# shemLamps.net
KiCad netlist of a schematic drawn in EAGLE
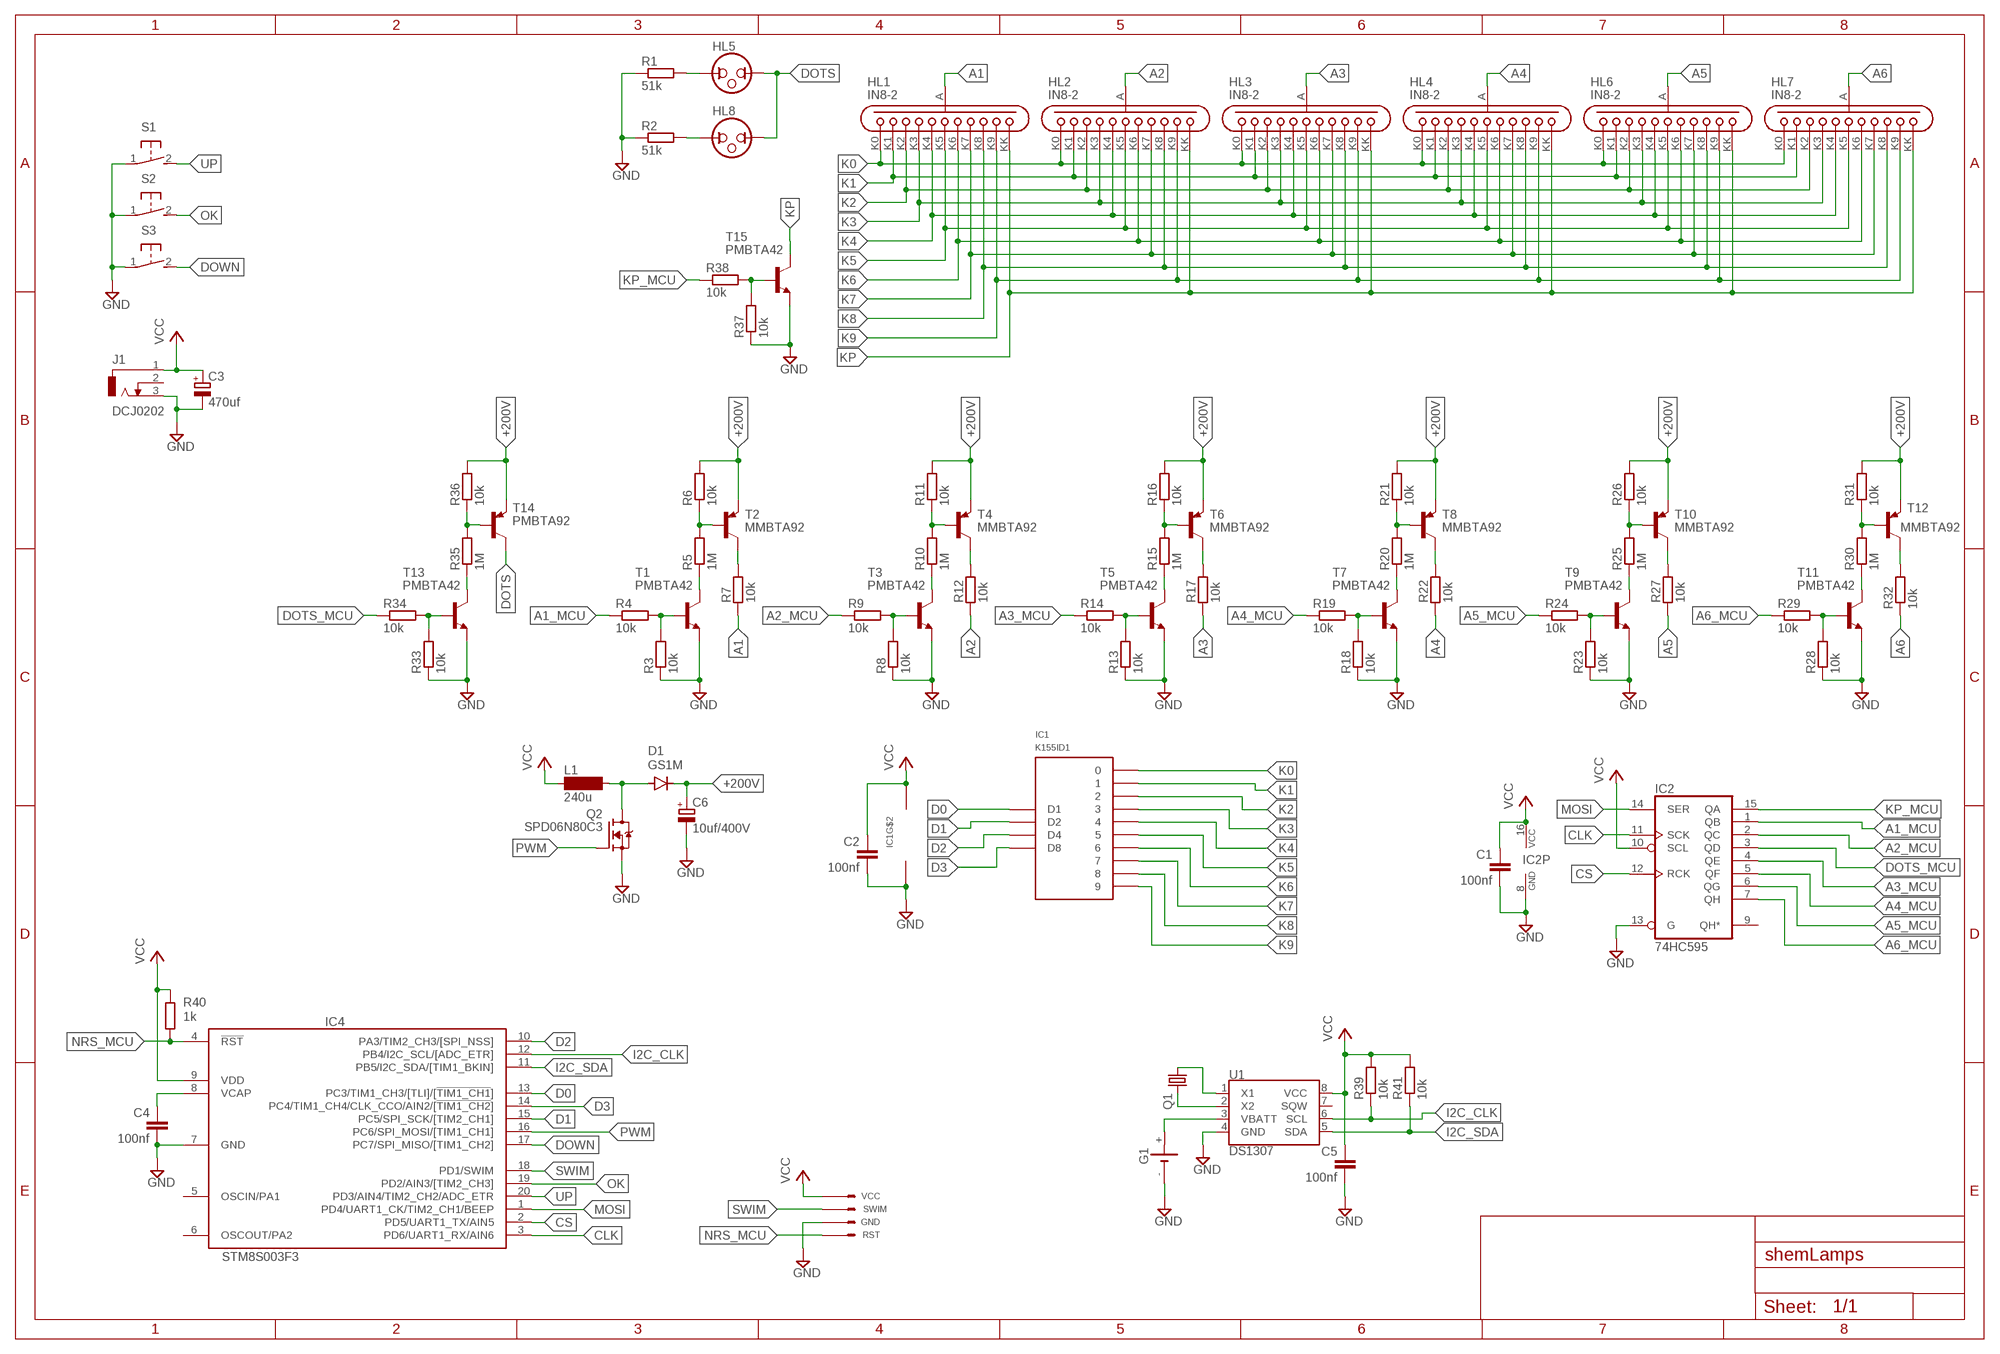
[diagram p0: schematic, sheet 1]

(export (version "E")
  (design (tool "Eeschema 10.0.6"))
  (components
    (comp (ref "C1")
      (value "100nf")
      (footprint "eagle-import:C0805")
      (libsource (lib "eagle-import") (part "CAP"))
    )
    (comp (ref "C2")
      (value "100nf")
      (footprint "eagle-import:C0805")
      (libsource (lib "eagle-import") (part "CAP"))
    )
    (comp (ref "C3")
      (value "470uf")
      (footprint "eagle-import:E3,5-8")
      (libsource (lib "eagle-import") (part "CPOL-EUE3.5-8"))
    )
    (comp (ref "C4")
      (value "100nf")
      (footprint "eagle-import:C0805")
      (libsource (lib "eagle-import") (part "CAP"))
    )
    (comp (ref "C5")
      (value "100nf")
      (footprint "eagle-import:C0805")
      (libsource (lib "eagle-import") (part "CAP"))
    )
    (comp (ref "C6")
      (value "10uf/400V")
      (footprint "eagle-import:E3,5-8")
      (libsource (lib "eagle-import") (part "CPOL-EUE3.5-8"))
    )
    (comp (ref "D1")
      (value "GS1M")
      (footprint "eagle-import:DO-214AC")
      (libsource (lib "eagle-import") (part "DIODE-DO-214AC"))
    )
    (comp (ref "G1")
      (value "BATTERY")
      (footprint "eagle-import:CH291-1220LF_W")
      (libsource (lib "eagle-import") (part "BATTERY"))
    )
    (comp (ref "HL1")
      (value "IN8-2")
      (footprint "eagle-import:IN8-2")
      (libsource (lib "eagle-import") (part "IN8-2"))
    )
    (comp (ref "HL2")
      (value "IN8-2")
      (footprint "eagle-import:IN8-2")
      (libsource (lib "eagle-import") (part "IN8-2"))
    )
    (comp (ref "HL3")
      (value "IN8-2")
      (footprint "eagle-import:IN8-2")
      (libsource (lib "eagle-import") (part "IN8-2"))
    )
    (comp (ref "HL4")
      (value "IN8-2")
      (footprint "eagle-import:IN8-2")
      (libsource (lib "eagle-import") (part "IN8-2"))
    )
    (comp (ref "HL5")
      (value "NEON_LAMP")
      (footprint "eagle-import:NEON_LAMP")
      (libsource (lib "eagle-import") (part "NEON_LAMP"))
    )
    (comp (ref "HL6")
      (value "IN8-2")
      (footprint "eagle-import:IN8-2")
      (libsource (lib "eagle-import") (part "IN8-2"))
    )
    (comp (ref "HL7")
      (value "IN8-2")
      (footprint "eagle-import:IN8-2")
      (libsource (lib "eagle-import") (part "IN8-2"))
    )
    (comp (ref "HL8")
      (value "NEON_LAMP")
      (footprint "eagle-import:NEON_LAMP")
      (libsource (lib "eagle-import") (part "NEON_LAMP"))
    )
    (comp (ref "IC1")
      (value "K155ID1")
      (footprint "eagle-import:DIL16")
      (libsource (lib "eagle-import") (part "K155ID1"))
    )
    (comp (ref "IC2")
      (value "74HC595")
      (footprint "eagle-import:TSSOP16L")
      (libsource (lib "eagle-import") (part "74HC595"))
    )
    (comp (ref "IC4")
      (value "STM8S003F3")
      (footprint "eagle-import:TSSOP20")
      (libsource (lib "eagle-import") (part "STM8S003F3"))
    )
    (comp (ref "J1")
      (value "DCJ0202")
      (footprint "eagle-import:DCJ0202")
      (libsource (lib "eagle-import") (part "DCJ0202"))
    )
    (comp (ref "L1")
      (value "240u")
      (footprint "eagle-import:BS11")
      (libsource (lib "eagle-import") (part "BS11"))
    )
    (comp (ref "Q1")
      (value "CRYSTALTC26H")
      (footprint "eagle-import:TC26H")
      (libsource (lib "eagle-import") (part "CRYSTALTC26H"))
    )
    (comp (ref "Q2")
      (value "SPD06N80C3")
      (footprint "eagle-import:TO252")
      (libsource (lib "eagle-import") (part "SPD06N80C3"))
    )
    (comp (ref "R1")
      (value "51k")
      (footprint "eagle-import:0207_10")
      (libsource (lib "eagle-import") (part "R-EU_0207/10"))
    )
    (comp (ref "R2")
      (value "51k")
      (footprint "eagle-import:0207_10")
      (libsource (lib "eagle-import") (part "R-EU_0207/10"))
    )
    (comp (ref "R3")
      (value "10k")
      (footprint "eagle-import:R0805")
      (libsource (lib "eagle-import") (part "RES"))
    )
    (comp (ref "R4")
      (value "10k")
      (footprint "eagle-import:R0805")
      (libsource (lib "eagle-import") (part "RES"))
    )
    (comp (ref "R5")
      (value "1M")
      (footprint "eagle-import:R0805")
      (libsource (lib "eagle-import") (part "RES"))
    )
    (comp (ref "R6")
      (value "10k")
      (footprint "eagle-import:R0805")
      (libsource (lib "eagle-import") (part "RES"))
    )
    (comp (ref "R7")
      (value "10k")
      (footprint "eagle-import:R0805")
      (libsource (lib "eagle-import") (part "RES"))
    )
    (comp (ref "R8")
      (value "10k")
      (footprint "eagle-import:R0805")
      (libsource (lib "eagle-import") (part "RES"))
    )
    (comp (ref "R9")
      (value "10k")
      (footprint "eagle-import:R0805")
      (libsource (lib "eagle-import") (part "RES"))
    )
    (comp (ref "R10")
      (value "1M")
      (footprint "eagle-import:R0805")
      (libsource (lib "eagle-import") (part "RES"))
    )
    (comp (ref "R11")
      (value "10k")
      (footprint "eagle-import:R0805")
      (libsource (lib "eagle-import") (part "RES"))
    )
    (comp (ref "R12")
      (value "10k")
      (footprint "eagle-import:R0805")
      (libsource (lib "eagle-import") (part "RES"))
    )
    (comp (ref "R13")
      (value "10k")
      (footprint "eagle-import:R0805")
      (libsource (lib "eagle-import") (part "RES"))
    )
    (comp (ref "R14")
      (value "10k")
      (footprint "eagle-import:R0805")
      (libsource (lib "eagle-import") (part "RES"))
    )
    (comp (ref "R15")
      (value "1M")
      (footprint "eagle-import:R0805")
      (libsource (lib "eagle-import") (part "RES"))
    )
    (comp (ref "R16")
      (value "10k")
      (footprint "eagle-import:R0805")
      (libsource (lib "eagle-import") (part "RES"))
    )
    (comp (ref "R17")
      (value "10k")
      (footprint "eagle-import:R0805")
      (libsource (lib "eagle-import") (part "RES"))
    )
    (comp (ref "R18")
      (value "10k")
      (footprint "eagle-import:R0805")
      (libsource (lib "eagle-import") (part "RES"))
    )
    (comp (ref "R19")
      (value "10k")
      (footprint "eagle-import:R0805")
      (libsource (lib "eagle-import") (part "RES"))
    )
    (comp (ref "R20")
      (value "1M")
      (footprint "eagle-import:R0805")
      (libsource (lib "eagle-import") (part "RES"))
    )
    (comp (ref "R21")
      (value "10k")
      (footprint "eagle-import:R0805")
      (libsource (lib "eagle-import") (part "RES"))
    )
    (comp (ref "R22")
      (value "10k")
      (footprint "eagle-import:R0805")
      (libsource (lib "eagle-import") (part "RES"))
    )
    (comp (ref "R23")
      (value "10k")
      (footprint "eagle-import:R0805")
      (libsource (lib "eagle-import") (part "RES"))
    )
    (comp (ref "R24")
      (value "10k")
      (footprint "eagle-import:R0805")
      (libsource (lib "eagle-import") (part "RES"))
    )
    (comp (ref "R25")
      (value "1M")
      (footprint "eagle-import:R0805")
      (libsource (lib "eagle-import") (part "RES"))
    )
    (comp (ref "R26")
      (value "10k")
      (footprint "eagle-import:R0805")
      (libsource (lib "eagle-import") (part "RES"))
    )
    (comp (ref "R27")
      (value "10k")
      (footprint "eagle-import:R0805")
      (libsource (lib "eagle-import") (part "RES"))
    )
    (comp (ref "R28")
      (value "10k")
      (footprint "eagle-import:R0805")
      (libsource (lib "eagle-import") (part "RES"))
    )
    (comp (ref "R29")
      (value "10k")
      (footprint "eagle-import:R0805")
      (libsource (lib "eagle-import") (part "RES"))
    )
    (comp (ref "R30")
      (value "1M")
      (footprint "eagle-import:R0805")
      (libsource (lib "eagle-import") (part "RES"))
    )
    (comp (ref "R31")
      (value "10k")
      (footprint "eagle-import:R0805")
      (libsource (lib "eagle-import") (part "RES"))
    )
    (comp (ref "R32")
      (value "10k")
      (footprint "eagle-import:R0805")
      (libsource (lib "eagle-import") (part "RES"))
    )
    (comp (ref "R33")
      (value "10k")
      (footprint "eagle-import:R0805")
      (libsource (lib "eagle-import") (part "RES"))
    )
    (comp (ref "R34")
      (value "10k")
      (footprint "eagle-import:R0805")
      (libsource (lib "eagle-import") (part "RES"))
    )
    (comp (ref "R35")
      (value "1M")
      (footprint "eagle-import:R0805")
      (libsource (lib "eagle-import") (part "RES"))
    )
    (comp (ref "R36")
      (value "10k")
      (footprint "eagle-import:R0805")
      (libsource (lib "eagle-import") (part "RES"))
    )
    (comp (ref "R37")
      (value "10k")
      (footprint "eagle-import:R0805")
      (libsource (lib "eagle-import") (part "RES"))
    )
    (comp (ref "R38")
      (value "10k")
      (footprint "eagle-import:R0805")
      (libsource (lib "eagle-import") (part "RES"))
    )
    (comp (ref "R39")
      (value "10k")
      (footprint "eagle-import:R0805")
      (libsource (lib "eagle-import") (part "RES"))
    )
    (comp (ref "R40")
      (value "1k")
      (footprint "eagle-import:R0805")
      (libsource (lib "eagle-import") (part "RES"))
    )
    (comp (ref "R41")
      (value "10k")
      (footprint "eagle-import:R0805")
      (libsource (lib "eagle-import") (part "RES"))
    )
    (comp (ref "S1")
      (value "31-XX")
      (footprint "eagle-import:B3F-31XX")
      (fields (field (name "MPN") "B3F-3100"))
      (libsource (lib "eagle-import") (part "31-XX"))
    )
    (comp (ref "S2")
      (value "31-XX")
      (footprint "eagle-import:B3F-31XX")
      (fields (field (name "MPN") "B3F-3100"))
      (libsource (lib "eagle-import") (part "31-XX"))
    )
    (comp (ref "S3")
      (value "31-XX")
      (footprint "eagle-import:B3F-31XX")
      (fields (field (name "MPN") "B3F-3100"))
      (libsource (lib "eagle-import") (part "31-XX"))
    )
    (comp (ref "SV1")
      (value "SWIM")
      (footprint "eagle-import:SWIM")
      (libsource (lib "eagle-import") (part "SWIM"))
    )
    (comp (ref "T1")
      (value "PMBTA42")
      (footprint "eagle-import:SOT23-BEC")
      (libsource (lib "eagle-import") (part "-NPN-SOT23-BECBC817-16"))
    )
    (comp (ref "T2")
      (value "MMBTA92")
      (footprint "eagle-import:SOT23-BEC")
      (libsource (lib "eagle-import") (part "-PNP-SOT23-BECBC807-16"))
    )
    (comp (ref "T3")
      (value "PMBTA42")
      (footprint "eagle-import:SOT23-BEC")
      (libsource (lib "eagle-import") (part "-NPN-SOT23-BECBC817-16"))
    )
    (comp (ref "T4")
      (value "MMBTA92")
      (footprint "eagle-import:SOT23-BEC")
      (libsource (lib "eagle-import") (part "-PNP-SOT23-BECBC807-16"))
    )
    (comp (ref "T5")
      (value "PMBTA42")
      (footprint "eagle-import:SOT23-BEC")
      (libsource (lib "eagle-import") (part "-NPN-SOT23-BECBC817-16"))
    )
    (comp (ref "T6")
      (value "MMBTA92")
      (footprint "eagle-import:SOT23-BEC")
      (libsource (lib "eagle-import") (part "-PNP-SOT23-BECBC807-16"))
    )
    (comp (ref "T7")
      (value "PMBTA42")
      (footprint "eagle-import:SOT23-BEC")
      (libsource (lib "eagle-import") (part "-NPN-SOT23-BECBC817-16"))
    )
    (comp (ref "T8")
      (value "MMBTA92")
      (footprint "eagle-import:SOT23-BEC")
      (libsource (lib "eagle-import") (part "-PNP-SOT23-BECBC807-16"))
    )
    (comp (ref "T9")
      (value "PMBTA42")
      (footprint "eagle-import:SOT23-BEC")
      (libsource (lib "eagle-import") (part "-NPN-SOT23-BECBC817-16"))
    )
    (comp (ref "T10")
      (value "MMBTA92")
      (footprint "eagle-import:SOT23-BEC")
      (libsource (lib "eagle-import") (part "-PNP-SOT23-BECBC807-16"))
    )
    (comp (ref "T11")
      (value "PMBTA42")
      (footprint "eagle-import:SOT23-BEC")
      (libsource (lib "eagle-import") (part "-NPN-SOT23-BECBC817-16"))
    )
    (comp (ref "T12")
      (value "MMBTA92")
      (footprint "eagle-import:SOT23-BEC")
      (libsource (lib "eagle-import") (part "-PNP-SOT23-BECBC807-16"))
    )
    (comp (ref "T13")
      (value "PMBTA42")
      (footprint "eagle-import:SOT23-BEC")
      (libsource (lib "eagle-import") (part "-NPN-SOT23-BECBC817-16"))
    )
    (comp (ref "T14")
      (value "PMBTA92")
      (footprint "eagle-import:SOT23-BEC")
      (libsource (lib "eagle-import") (part "-PNP-SOT23-BECBC807-16"))
    )
    (comp (ref "T15")
      (value "PMBTA42")
      (footprint "eagle-import:SOT23-BEC")
      (libsource (lib "eagle-import") (part "-NPN-SOT23-BECBC817-16"))
    )
    (comp (ref "U1")
      (value "DS1307")
      (footprint "eagle-import:SO08")
      (libsource (lib "eagle-import") (part "DS1307"))
    )
  )
  (nets
    (net (code "1") (name "+200V") (class "Default")
      (node (ref "C6") (pin "+") (pinfunction "+_+") (pintype "passive"))
      (node (ref "D1") (pin "C") (pinfunction "C_C") (pintype "passive"))
      (node (ref "R11") (pin "2") (pinfunction "2_2") (pintype "passive"))
      (node (ref "R16") (pin "2") (pinfunction "2_2") (pintype "passive"))
      (node (ref "R21") (pin "2") (pinfunction "2_2") (pintype "passive"))
      (node (ref "R26") (pin "2") (pinfunction "2_2") (pintype "passive"))
      (node (ref "R31") (pin "2") (pinfunction "2_2") (pintype "passive"))
      (node (ref "R36") (pin "2") (pinfunction "2_2") (pintype "passive"))
      (node (ref "R6") (pin "2") (pinfunction "2_2") (pintype "passive"))
      (node (ref "T10") (pin "E") (pinfunction "E_E") (pintype "passive"))
      (node (ref "T12") (pin "E") (pinfunction "E_E") (pintype "passive"))
      (node (ref "T14") (pin "E") (pinfunction "E_E") (pintype "passive"))
      (node (ref "T2") (pin "E") (pinfunction "E_E") (pintype "passive"))
      (node (ref "T4") (pin "E") (pinfunction "E_E") (pintype "passive"))
      (node (ref "T6") (pin "E") (pinfunction "E_E") (pintype "passive"))
      (node (ref "T8") (pin "E") (pinfunction "E_E") (pintype "passive"))
    )
    (net (code "2") (name "A1") (class "Default")
      (node (ref "HL1") (pin "A") (pinfunction "A_A") (pintype "passive"))
      (node (ref "R7") (pin "1") (pinfunction "1_1") (pintype "passive"))
    )
    (net (code "3") (name "A1_MCU") (class "Default")
      (node (ref "IC2") (pin "1") (pinfunction "QB_1") (pintype "tri_state"))
      (node (ref "R4") (pin "1") (pinfunction "1_1") (pintype "passive"))
    )
    (net (code "4") (name "A2") (class "Default")
      (node (ref "HL2") (pin "A") (pinfunction "A_A") (pintype "passive"))
      (node (ref "R12") (pin "1") (pinfunction "1_1") (pintype "passive"))
    )
    (net (code "5") (name "A2_MCU") (class "Default")
      (node (ref "IC2") (pin "2") (pinfunction "QC_2") (pintype "tri_state"))
      (node (ref "R9") (pin "1") (pinfunction "1_1") (pintype "passive"))
    )
    (net (code "6") (name "A3") (class "Default")
      (node (ref "HL3") (pin "A") (pinfunction "A_A") (pintype "passive"))
      (node (ref "R17") (pin "1") (pinfunction "1_1") (pintype "passive"))
    )
    (net (code "7") (name "A3_MCU") (class "Default")
      (node (ref "IC2") (pin "4") (pinfunction "QE_4") (pintype "tri_state"))
      (node (ref "R14") (pin "1") (pinfunction "1_1") (pintype "passive"))
    )
    (net (code "8") (name "A4") (class "Default")
      (node (ref "HL4") (pin "A") (pinfunction "A_A") (pintype "passive"))
      (node (ref "R22") (pin "1") (pinfunction "1_1") (pintype "passive"))
    )
    (net (code "9") (name "A4_MCU") (class "Default")
      (node (ref "IC2") (pin "5") (pinfunction "QF_5") (pintype "tri_state"))
      (node (ref "R19") (pin "1") (pinfunction "1_1") (pintype "passive"))
    )
    (net (code "10") (name "A5") (class "Default")
      (node (ref "HL6") (pin "A") (pinfunction "A_A") (pintype "passive"))
      (node (ref "R27") (pin "1") (pinfunction "1_1") (pintype "passive"))
    )
    (net (code "11") (name "A5_MCU") (class "Default")
      (node (ref "IC2") (pin "6") (pinfunction "QG_6") (pintype "tri_state"))
      (node (ref "R24") (pin "1") (pinfunction "1_1") (pintype "passive"))
    )
    (net (code "12") (name "A6") (class "Default")
      (node (ref "HL7") (pin "A") (pinfunction "A_A") (pintype "passive"))
      (node (ref "R32") (pin "1") (pinfunction "1_1") (pintype "passive"))
    )
    (net (code "13") (name "A6_MCU") (class "Default")
      (node (ref "IC2") (pin "7") (pinfunction "QH_7") (pintype "tri_state"))
      (node (ref "R29") (pin "1") (pinfunction "1_1") (pintype "passive"))
    )
    (net (code "14") (name "CLK") (class "Default")
      (node (ref "IC2") (pin "11") (pinfunction "SCK_11") (pintype "input"))
      (node (ref "IC4") (pin "3") (pinfunction "PD6/UART1_RX/AIN6_3") (pintype "bidirectional"))
    )
    (net (code "15") (name "CS") (class "Default")
      (node (ref "IC2") (pin "12") (pinfunction "RCK_12") (pintype "input"))
      (node (ref "IC4") (pin "2") (pinfunction "PD5/UART1_TX/AIN5_2") (pintype "bidirectional"))
    )
    (net (code "16") (name "D0") (class "Default")
      (node (ref "IC1") (pin "3") (pinfunction "D1_3") (pintype "input"))
      (node (ref "IC4") (pin "13") (pinfunction "PC3/TIM1_CH3/[TLI]/[~{TIM1_CH1}]_13") (pintype "bidirectional"))
    )
    (net (code "17") (name "D1") (class "Default")
      (node (ref "IC1") (pin "6") (pinfunction "D2_6") (pintype "input"))
      (node (ref "IC4") (pin "15") (pinfunction "PC5/SPI_SCK/[TIM2_CH1]_15") (pintype "bidirectional"))
    )
    (net (code "18") (name "D2") (class "Default")
      (node (ref "IC1") (pin "7") (pinfunction "D4_7") (pintype "input"))
      (node (ref "IC4") (pin "10") (pinfunction "PA3/TIM2_CH3/[SPI_NSS]_10") (pintype "bidirectional"))
    )
    (net (code "19") (name "D3") (class "Default")
      (node (ref "IC1") (pin "4") (pinfunction "D8_4") (pintype "input"))
      (node (ref "IC4") (pin "14") (pinfunction "PC4/TIM1_CH4/CLK_CCO/AIN2/[~{TIM1_CH2}]_14") (pintype "bidirectional"))
    )
    (net (code "20") (name "DOTS") (class "Default")
      (node (ref "HL5") (pin "2") (pinfunction "2_2") (pintype "passive"))
      (node (ref "HL8") (pin "2") (pinfunction "2_2") (pintype "passive"))
      (node (ref "T14") (pin "C") (pinfunction "C_C") (pintype "passive"))
    )
    (net (code "21") (name "DOTS_MCU") (class "Default")
      (node (ref "IC2") (pin "3") (pinfunction "QD_3") (pintype "tri_state"))
      (node (ref "R34") (pin "1") (pinfunction "1_1") (pintype "passive"))
    )
    (net (code "22") (name "DOWN") (class "Default")
      (node (ref "IC4") (pin "17") (pinfunction "PC7/SPI_MISO/[TIM1_CH2]_17") (pintype "bidirectional"))
      (node (ref "S3") (pin "2") (pinfunction "S_2") (pintype "passive"))
    )
    (net (code "23") (name "GND") (class "Default")
      (node (ref "C1") (pin "2") (pinfunction "2_2") (pintype "passive"))
      (node (ref "C2") (pin "2") (pinfunction "2_2") (pintype "passive"))
      (node (ref "C3") (pin "-") (pinfunction "-_-") (pintype "passive"))
      (node (ref "C4") (pin "2") (pinfunction "2_2") (pintype "passive"))
      (node (ref "C5") (pin "2") (pinfunction "2_2") (pintype "passive"))
      (node (ref "C6") (pin "-") (pinfunction "-_-") (pintype "passive"))
      (node (ref "G1") (pin "-") (pinfunction "-_-") (pintype "passive"))
      (node (ref "IC1") (pin "12") (pinfunction "GND_12") (pintype "power_in"))
      (node (ref "IC2") (pin "13") (pinfunction "G_13") (pintype "input"))
      (node (ref "IC2") (pin "8") (pinfunction "GND_8") (pintype "power_in"))
      (node (ref "IC4") (pin "7") (pinfunction "GND_7") (pintype "power_in"))
      (node (ref "J1") (pin "3") (pinfunction "3_3") (pintype "passive"))
      (node (ref "Q2") (pin "2") (pinfunction "S_2") (pintype "passive"))
      (node (ref "R1") (pin "1") (pinfunction "1_1") (pintype "passive"))
      (node (ref "R13") (pin "1") (pinfunction "1_1") (pintype "passive"))
      (node (ref "R18") (pin "1") (pinfunction "1_1") (pintype "passive"))
      (node (ref "R2") (pin "1") (pinfunction "1_1") (pintype "passive"))
      (node (ref "R23") (pin "1") (pinfunction "1_1") (pintype "passive"))
      (node (ref "R28") (pin "1") (pinfunction "1_1") (pintype "passive"))
      (node (ref "R3") (pin "1") (pinfunction "1_1") (pintype "passive"))
      (node (ref "R33") (pin "1") (pinfunction "1_1") (pintype "passive"))
      (node (ref "R37") (pin "1") (pinfunction "1_1") (pintype "passive"))
      (node (ref "R8") (pin "1") (pinfunction "1_1") (pintype "passive"))
      (node (ref "S1") (pin "1") (pinfunction "P_1") (pintype "passive"))
      (node (ref "S2") (pin "1") (pinfunction "P_1") (pintype "passive"))
      (node (ref "S3") (pin "1") (pinfunction "P_1") (pintype "passive"))
      (node (ref "SV1") (pin "GND") (pinfunction "GND_GND") (pintype "power_in"))
      (node (ref "T1") (pin "E") (pinfunction "E_E") (pintype "passive"))
      (node (ref "T11") (pin "E") (pinfunction "E_E") (pintype "passive"))
      (node (ref "T13") (pin "E") (pinfunction "E_E") (pintype "passive"))
      (node (ref "T15") (pin "E") (pinfunction "E_E") (pintype "passive"))
      (node (ref "T3") (pin "E") (pinfunction "E_E") (pintype "passive"))
      (node (ref "T5") (pin "E") (pinfunction "E_E") (pintype "passive"))
      (node (ref "T7") (pin "E") (pinfunction "E_E") (pintype "passive"))
      (node (ref "T9") (pin "E") (pinfunction "E_E") (pintype "passive"))
      (node (ref "U1") (pin "4") (pinfunction "GND_4") (pintype "bidirectional"))
    )
    (net (code "24") (name "I2C_CLK") (class "Default")
      (node (ref "IC4") (pin "12") (pinfunction "PB4/I2C_SCL/[ADC_ETR]_12") (pintype "bidirectional"))
      (node (ref "R39") (pin "1") (pinfunction "1_1") (pintype "passive"))
      (node (ref "U1") (pin "6") (pinfunction "SCL_6") (pintype "bidirectional"))
    )
    (net (code "25") (name "I2C_SDA") (class "Default")
      (node (ref "IC4") (pin "11") (pinfunction "PB5/I2C_SDA/[TIM1_BKIN]_11") (pintype "bidirectional"))
      (node (ref "R41") (pin "1") (pinfunction "1_1") (pintype "passive"))
      (node (ref "U1") (pin "5") (pinfunction "SDA_5") (pintype "bidirectional"))
    )
    (net (code "26") (name "K0") (class "Default")
      (node (ref "HL1") (pin "K0") (pinfunction "K0_K0") (pintype "passive"))
      (node (ref "HL2") (pin "K0") (pinfunction "K0_K0") (pintype "passive"))
      (node (ref "HL3") (pin "K0") (pinfunction "K0_K0") (pintype "passive"))
      (node (ref "HL4") (pin "K0") (pinfunction "K0_K0") (pintype "passive"))
      (node (ref "HL6") (pin "K0") (pinfunction "K0_K0") (pintype "passive"))
      (node (ref "HL7") (pin "K0") (pinfunction "K0_K0") (pintype "passive"))
      (node (ref "IC1") (pin "16") (pinfunction "0_16") (pintype "output"))
    )
    (net (code "27") (name "K1") (class "Default")
      (node (ref "HL1") (pin "K1") (pinfunction "K1_K1") (pintype "passive"))
      (node (ref "HL2") (pin "K1") (pinfunction "K1_K1") (pintype "passive"))
      (node (ref "HL3") (pin "K1") (pinfunction "K1_K1") (pintype "passive"))
      (node (ref "HL4") (pin "K1") (pinfunction "K1_K1") (pintype "passive"))
      (node (ref "HL6") (pin "K1") (pinfunction "K1_K1") (pintype "passive"))
      (node (ref "HL7") (pin "K1") (pinfunction "K1_K1") (pintype "passive"))
      (node (ref "IC1") (pin "15") (pinfunction "1_15") (pintype "output"))
    )
    (net (code "28") (name "K2") (class "Default")
      (node (ref "HL1") (pin "K2") (pinfunction "K2_K2") (pintype "passive"))
      (node (ref "HL2") (pin "K2") (pinfunction "K2_K2") (pintype "passive"))
      (node (ref "HL3") (pin "K2") (pinfunction "K2_K2") (pintype "passive"))
      (node (ref "HL4") (pin "K2") (pinfunction "K2_K2") (pintype "passive"))
      (node (ref "HL6") (pin "K2") (pinfunction "K2_K2") (pintype "passive"))
      (node (ref "HL7") (pin "K2") (pinfunction "K2_K2") (pintype "passive"))
      (node (ref "IC1") (pin "8") (pinfunction "2_8") (pintype "output"))
    )
    (net (code "29") (name "K3") (class "Default")
      (node (ref "HL1") (pin "K3") (pinfunction "K3_K3") (pintype "passive"))
      (node (ref "HL2") (pin "K3") (pinfunction "K3_K3") (pintype "passive"))
      (node (ref "HL3") (pin "K3") (pinfunction "K3_K3") (pintype "passive"))
      (node (ref "HL4") (pin "K3") (pinfunction "K3_K3") (pintype "passive"))
      (node (ref "HL6") (pin "K3") (pinfunction "K3_K3") (pintype "passive"))
      (node (ref "HL7") (pin "K3") (pinfunction "K3_K3") (pintype "passive"))
      (node (ref "IC1") (pin "9") (pinfunction "3_9") (pintype "output"))
    )
    (net (code "30") (name "K4") (class "Default")
      (node (ref "HL1") (pin "K4") (pinfunction "K4_K4") (pintype "passive"))
      (node (ref "HL2") (pin "K4") (pinfunction "K4_K4") (pintype "passive"))
      (node (ref "HL3") (pin "K4") (pinfunction "K4_K4") (pintype "passive"))
      (node (ref "HL4") (pin "K4") (pinfunction "K4_K4") (pintype "passive"))
      (node (ref "HL6") (pin "K4") (pinfunction "K4_K4") (pintype "passive"))
      (node (ref "HL7") (pin "K4") (pinfunction "K4_K4") (pintype "passive"))
      (node (ref "IC1") (pin "13") (pinfunction "4_13") (pintype "output"))
    )
    (net (code "31") (name "K5") (class "Default")
      (node (ref "HL1") (pin "K5") (pinfunction "K5_K5") (pintype "passive"))
      (node (ref "HL2") (pin "K5") (pinfunction "K5_K5") (pintype "passive"))
      (node (ref "HL3") (pin "K5") (pinfunction "K5_K5") (pintype "passive"))
      (node (ref "HL4") (pin "K5") (pinfunction "K5_K5") (pintype "passive"))
      (node (ref "HL6") (pin "K5") (pinfunction "K5_K5") (pintype "passive"))
      (node (ref "HL7") (pin "K5") (pinfunction "K5_K5") (pintype "passive"))
      (node (ref "IC1") (pin "14") (pinfunction "5_14") (pintype "output"))
    )
    (net (code "32") (name "K6") (class "Default")
      (node (ref "HL1") (pin "K6") (pinfunction "K6_K6") (pintype "passive"))
      (node (ref "HL2") (pin "K6") (pinfunction "K6_K6") (pintype "passive"))
      (node (ref "HL3") (pin "K6") (pinfunction "K6_K6") (pintype "passive"))
      (node (ref "HL4") (pin "K6") (pinfunction "K6_K6") (pintype "passive"))
      (node (ref "HL6") (pin "K6") (pinfunction "K6_K6") (pintype "passive"))
      (node (ref "HL7") (pin "K6") (pinfunction "K6_K6") (pintype "passive"))
      (node (ref "IC1") (pin "11") (pinfunction "6_11") (pintype "output"))
    )
    (net (code "33") (name "K7") (class "Default")
      (node (ref "HL1") (pin "K7") (pinfunction "K7_K7") (pintype "passive"))
      (node (ref "HL2") (pin "K7") (pinfunction "K7_K7") (pintype "passive"))
      (node (ref "HL3") (pin "K7") (pinfunction "K7_K7") (pintype "passive"))
      (node (ref "HL4") (pin "K7") (pinfunction "K7_K7") (pintype "passive"))
      (node (ref "HL6") (pin "K7") (pinfunction "K7_K7") (pintype "passive"))
      (node (ref "HL7") (pin "K7") (pinfunction "K7_K7") (pintype "passive"))
      (node (ref "IC1") (pin "10") (pinfunction "7_10") (pintype "output"))
    )
    (net (code "34") (name "K8") (class "Default")
      (node (ref "HL1") (pin "K8") (pinfunction "K8_K8") (pintype "passive"))
      (node (ref "HL2") (pin "K8") (pinfunction "K8_K8") (pintype "passive"))
      (node (ref "HL3") (pin "K8") (pinfunction "K8_K8") (pintype "passive"))
      (node (ref "HL4") (pin "K8") (pinfunction "K8_K8") (pintype "passive"))
      (node (ref "HL6") (pin "K8") (pinfunction "K8_K8") (pintype "passive"))
      (node (ref "HL7") (pin "K8") (pinfunction "K8_K8") (pintype "passive"))
      (node (ref "IC1") (pin "1") (pinfunction "8_1") (pintype "output"))
    )
    (net (code "35") (name "K9") (class "Default")
      (node (ref "HL1") (pin "K9") (pinfunction "K9_K9") (pintype "passive"))
      (node (ref "HL2") (pin "K9") (pinfunction "K9_K9") (pintype "passive"))
      (node (ref "HL3") (pin "K9") (pinfunction "K9_K9") (pintype "passive"))
      (node (ref "HL4") (pin "K9") (pinfunction "K9_K9") (pintype "passive"))
      (node (ref "HL6") (pin "K9") (pinfunction "K9_K9") (pintype "passive"))
      (node (ref "HL7") (pin "K9") (pinfunction "K9_K9") (pintype "passive"))
      (node (ref "IC1") (pin "2") (pinfunction "9_2") (pintype "output"))
    )
    (net (code "36") (name "KP") (class "Default")
      (node (ref "HL1") (pin "KK") (pinfunction "KK_KK") (pintype "passive"))
      (node (ref "HL2") (pin "KK") (pinfunction "KK_KK") (pintype "passive"))
      (node (ref "HL3") (pin "KK") (pinfunction "KK_KK") (pintype "passive"))
      (node (ref "HL4") (pin "KK") (pinfunction "KK_KK") (pintype "passive"))
      (node (ref "HL6") (pin "KK") (pinfunction "KK_KK") (pintype "passive"))
      (node (ref "HL7") (pin "KK") (pinfunction "KK_KK") (pintype "passive"))
      (node (ref "T15") (pin "C") (pinfunction "C_C") (pintype "passive"))
    )
    (net (code "37") (name "KP_MCU") (class "Default")
      (node (ref "IC2") (pin "15") (pinfunction "QA_15") (pintype "tri_state"))
      (node (ref "R38") (pin "1") (pinfunction "1_1") (pintype "passive"))
    )
    (net (code "38") (name "MOSI") (class "Default")
      (node (ref "IC2") (pin "14") (pinfunction "SER_14") (pintype "input"))
      (node (ref "IC4") (pin "1") (pinfunction "PD4/UART1_CK/TIM2_CH1/BEEP_1") (pintype "bidirectional"))
    )
    (net (code "39") (name "NRS_MCU") (class "Default")
      (node (ref "IC4") (pin "4") (pinfunction "~{RST}_4") (pintype "input"))
      (node (ref "R40") (pin "1") (pinfunction "1_1") (pintype "passive"))
      (node (ref "SV1") (pin "NRS") (pinfunction "RST_NRS") (pintype "bidirectional"))
    )
    (net (code "40") (name "Net-(HL5-Pad1)") (class "Default")
      (node (ref "HL5") (pin "1") (pinfunction "1_1") (pintype "passive"))
      (node (ref "R1") (pin "2") (pinfunction "2_2") (pintype "passive"))
    )
    (net (code "41") (name "Net-(HL8-Pad1)") (class "Default")
      (node (ref "HL8") (pin "1") (pinfunction "1_1") (pintype "passive"))
      (node (ref "R2") (pin "2") (pinfunction "2_2") (pintype "passive"))
    )
    (net (code "42") (name "Net-(IC4-VCAP)") (class "Default")
      (node (ref "C4") (pin "1") (pinfunction "1_1") (pintype "passive"))
      (node (ref "IC4") (pin "8") (pinfunction "VCAP_8") (pintype "power_in"))
    )
    (net (code "43") (name "Net-(Q2-D)") (class "Default")
      (node (ref "D1") (pin "A") (pinfunction "A_A") (pintype "passive"))
      (node (ref "L1") (pin "2") (pinfunction "2_2") (pintype "passive"))
      (node (ref "Q2") (pin "3") (pinfunction "D_3") (pintype "passive"))
    )
    (net (code "44") (name "Net-(R3-Pad2)") (class "Default")
      (node (ref "R3") (pin "2") (pinfunction "2_2") (pintype "passive"))
      (node (ref "R4") (pin "2") (pinfunction "2_2") (pintype "passive"))
      (node (ref "T1") (pin "B") (pinfunction "B_B") (pintype "passive"))
    )
    (net (code "45") (name "Net-(R5-Pad1)") (class "Default")
      (node (ref "R5") (pin "1") (pinfunction "1_1") (pintype "passive"))
      (node (ref "T1") (pin "C") (pinfunction "C_C") (pintype "passive"))
    )
    (net (code "46") (name "Net-(R5-Pad2)") (class "Default")
      (node (ref "R5") (pin "2") (pinfunction "2_2") (pintype "passive"))
      (node (ref "R6") (pin "1") (pinfunction "1_1") (pintype "passive"))
      (node (ref "T2") (pin "B") (pinfunction "B_B") (pintype "passive"))
    )
    (net (code "47") (name "Net-(R7-Pad2)") (class "Default")
      (node (ref "R7") (pin "2") (pinfunction "2_2") (pintype "passive"))
      (node (ref "T2") (pin "C") (pinfunction "C_C") (pintype "passive"))
    )
    (net (code "48") (name "Net-(R8-Pad2)") (class "Default")
      (node (ref "R8") (pin "2") (pinfunction "2_2") (pintype "passive"))
      (node (ref "R9") (pin "2") (pinfunction "2_2") (pintype "passive"))
      (node (ref "T3") (pin "B") (pinfunction "B_B") (pintype "passive"))
    )
    (net (code "49") (name "Net-(R10-Pad1)") (class "Default")
      (node (ref "R10") (pin "1") (pinfunction "1_1") (pintype "passive"))
      (node (ref "T3") (pin "C") (pinfunction "C_C") (pintype "passive"))
    )
    (net (code "50") (name "Net-(R10-Pad2)") (class "Default")
      (node (ref "R10") (pin "2") (pinfunction "2_2") (pintype "passive"))
      (node (ref "R11") (pin "1") (pinfunction "1_1") (pintype "passive"))
      (node (ref "T4") (pin "B") (pinfunction "B_B") (pintype "passive"))
    )
    (net (code "51") (name "Net-(R12-Pad2)") (class "Default")
      (node (ref "R12") (pin "2") (pinfunction "2_2") (pintype "passive"))
      (node (ref "T4") (pin "C") (pinfunction "C_C") (pintype "passive"))
    )
    (net (code "52") (name "Net-(R13-Pad2)") (class "Default")
      (node (ref "R13") (pin "2") (pinfunction "2_2") (pintype "passive"))
      (node (ref "R14") (pin "2") (pinfunction "2_2") (pintype "passive"))
      (node (ref "T5") (pin "B") (pinfunction "B_B") (pintype "passive"))
    )
    (net (code "53") (name "Net-(R15-Pad1)") (class "Default")
      (node (ref "R15") (pin "1") (pinfunction "1_1") (pintype "passive"))
      (node (ref "T5") (pin "C") (pinfunction "C_C") (pintype "passive"))
    )
    (net (code "54") (name "Net-(R15-Pad2)") (class "Default")
      (node (ref "R15") (pin "2") (pinfunction "2_2") (pintype "passive"))
      (node (ref "R16") (pin "1") (pinfunction "1_1") (pintype "passive"))
      (node (ref "T6") (pin "B") (pinfunction "B_B") (pintype "passive"))
    )
    (net (code "55") (name "Net-(R17-Pad2)") (class "Default")
      (node (ref "R17") (pin "2") (pinfunction "2_2") (pintype "passive"))
      (node (ref "T6") (pin "C") (pinfunction "C_C") (pintype "passive"))
    )
    (net (code "56") (name "Net-(R18-Pad2)") (class "Default")
      (node (ref "R18") (pin "2") (pinfunction "2_2") (pintype "passive"))
      (node (ref "R19") (pin "2") (pinfunction "2_2") (pintype "passive"))
      (node (ref "T7") (pin "B") (pinfunction "B_B") (pintype "passive"))
    )
    (net (code "57") (name "Net-(R20-Pad1)") (class "Default")
      (node (ref "R20") (pin "1") (pinfunction "1_1") (pintype "passive"))
      (node (ref "T7") (pin "C") (pinfunction "C_C") (pintype "passive"))
    )
    (net (code "58") (name "Net-(R20-Pad2)") (class "Default")
      (node (ref "R20") (pin "2") (pinfunction "2_2") (pintype "passive"))
      (node (ref "R21") (pin "1") (pinfunction "1_1") (pintype "passive"))
      (node (ref "T8") (pin "B") (pinfunction "B_B") (pintype "passive"))
    )
    (net (code "59") (name "Net-(R22-Pad2)") (class "Default")
      (node (ref "R22") (pin "2") (pinfunction "2_2") (pintype "passive"))
      (node (ref "T8") (pin "C") (pinfunction "C_C") (pintype "passive"))
    )
    (net (code "60") (name "Net-(R23-Pad2)") (class "Default")
      (node (ref "R23") (pin "2") (pinfunction "2_2") (pintype "passive"))
      (node (ref "R24") (pin "2") (pinfunction "2_2") (pintype "passive"))
      (node (ref "T9") (pin "B") (pinfunction "B_B") (pintype "passive"))
    )
    (net (code "61") (name "Net-(R25-Pad1)") (class "Default")
      (node (ref "R25") (pin "1") (pinfunction "1_1") (pintype "passive"))
      (node (ref "T9") (pin "C") (pinfunction "C_C") (pintype "passive"))
    )
    (net (code "62") (name "Net-(R25-Pad2)") (class "Default")
      (node (ref "R25") (pin "2") (pinfunction "2_2") (pintype "passive"))
      (node (ref "R26") (pin "1") (pinfunction "1_1") (pintype "passive"))
      (node (ref "T10") (pin "B") (pinfunction "B_B") (pintype "passive"))
    )
    (net (code "63") (name "Net-(R27-Pad2)") (class "Default")
      (node (ref "R27") (pin "2") (pinfunction "2_2") (pintype "passive"))
      (node (ref "T10") (pin "C") (pinfunction "C_C") (pintype "passive"))
    )
    (net (code "64") (name "Net-(R28-Pad2)") (class "Default")
      (node (ref "R28") (pin "2") (pinfunction "2_2") (pintype "passive"))
      (node (ref "R29") (pin "2") (pinfunction "2_2") (pintype "passive"))
      (node (ref "T11") (pin "B") (pinfunction "B_B") (pintype "passive"))
    )
    (net (code "65") (name "Net-(R30-Pad1)") (class "Default")
      (node (ref "R30") (pin "1") (pinfunction "1_1") (pintype "passive"))
      (node (ref "T11") (pin "C") (pinfunction "C_C") (pintype "passive"))
    )
    (net (code "66") (name "Net-(R30-Pad2)") (class "Default")
      (node (ref "R30") (pin "2") (pinfunction "2_2") (pintype "passive"))
      (node (ref "R31") (pin "1") (pinfunction "1_1") (pintype "passive"))
      (node (ref "T12") (pin "B") (pinfunction "B_B") (pintype "passive"))
    )
    (net (code "67") (name "Net-(R32-Pad2)") (class "Default")
      (node (ref "R32") (pin "2") (pinfunction "2_2") (pintype "passive"))
      (node (ref "T12") (pin "C") (pinfunction "C_C") (pintype "passive"))
    )
    (net (code "68") (name "Net-(R33-Pad2)") (class "Default")
      (node (ref "R33") (pin "2") (pinfunction "2_2") (pintype "passive"))
      (node (ref "R34") (pin "2") (pinfunction "2_2") (pintype "passive"))
      (node (ref "T13") (pin "B") (pinfunction "B_B") (pintype "passive"))
    )
    (net (code "69") (name "Net-(R35-Pad1)") (class "Default")
      (node (ref "R35") (pin "1") (pinfunction "1_1") (pintype "passive"))
      (node (ref "T13") (pin "C") (pinfunction "C_C") (pintype "passive"))
    )
    (net (code "70") (name "Net-(R35-Pad2)") (class "Default")
      (node (ref "R35") (pin "2") (pinfunction "2_2") (pintype "passive"))
      (node (ref "R36") (pin "1") (pinfunction "1_1") (pintype "passive"))
      (node (ref "T14") (pin "B") (pinfunction "B_B") (pintype "passive"))
    )
    (net (code "71") (name "Net-(R37-Pad2)") (class "Default")
      (node (ref "R37") (pin "2") (pinfunction "2_2") (pintype "passive"))
      (node (ref "R38") (pin "2") (pinfunction "2_2") (pintype "passive"))
      (node (ref "T15") (pin "B") (pinfunction "B_B") (pintype "passive"))
    )
    (net (code "72") (name "Net-(U1-VBATT)") (class "Default")
      (node (ref "G1") (pin "+") (pinfunction "+_+") (pintype "passive"))
      (node (ref "U1") (pin "3") (pinfunction "VBATT_3") (pintype "bidirectional"))
    )
    (net (code "73") (name "Net-(U1-X1)") (class "Default")
      (node (ref "Q1") (pin "1") (pinfunction "1_1") (pintype "passive"))
      (node (ref "U1") (pin "1") (pinfunction "X1_1") (pintype "bidirectional"))
    )
    (net (code "74") (name "Net-(U1-X2)") (class "Default")
      (node (ref "Q1") (pin "2") (pinfunction "2_2") (pintype "passive"))
      (node (ref "U1") (pin "2") (pinfunction "X2_2") (pintype "bidirectional"))
    )
    (net (code "75") (name "OK") (class "Default")
      (node (ref "IC4") (pin "19") (pinfunction "PD2/AIN3/[TIM2_CH3]_19") (pintype "bidirectional"))
      (node (ref "S2") (pin "2") (pinfunction "S_2") (pintype "passive"))
    )
    (net (code "76") (name "PWM") (class "Default")
      (node (ref "IC4") (pin "16") (pinfunction "PC6/SPI_MOSI/[TIM1_CH1]_16") (pintype "bidirectional"))
      (node (ref "Q2") (pin "1") (pinfunction "G_1") (pintype "passive"))
    )
    (net (code "77") (name "SWIM") (class "Default")
      (node (ref "IC4") (pin "18") (pinfunction "PD1/SWIM_18") (pintype "bidirectional"))
      (node (ref "SV1") (pin "SWIM") (pinfunction "SWIM_SWIM") (pintype "bidirectional"))
    )
    (net (code "78") (name "UP") (class "Default")
      (node (ref "IC4") (pin "20") (pinfunction "PD3/AIN4/TIM2_CH2/ADC_ETR_20") (pintype "bidirectional"))
      (node (ref "S1") (pin "2") (pinfunction "S_2") (pintype "passive"))
    )
    (net (code "79") (name "VCC") (class "Default")
      (node (ref "C1") (pin "1") (pinfunction "1_1") (pintype "passive"))
      (node (ref "C2") (pin "1") (pinfunction "1_1") (pintype "passive"))
      (node (ref "C3") (pin "+") (pinfunction "+_+") (pintype "passive"))
      (node (ref "C5") (pin "1") (pinfunction "1_1") (pintype "passive"))
      (node (ref "IC1") (pin "5") (pinfunction "VCC_5") (pintype "power_in"))
      (node (ref "IC2") (pin "10") (pinfunction "SCL_10") (pintype "input"))
      (node (ref "IC2") (pin "16") (pinfunction "VCC_16") (pintype "power_in"))
      (node (ref "IC4") (pin "9") (pinfunction "VDD_9") (pintype "power_in"))
      (node (ref "J1") (pin "1") (pinfunction "1_1") (pintype "passive"))
      (node (ref "L1") (pin "1") (pinfunction "1_1") (pintype "passive"))
      (node (ref "R39") (pin "2") (pinfunction "2_2") (pintype "passive"))
      (node (ref "R40") (pin "2") (pinfunction "2_2") (pintype "passive"))
      (node (ref "R41") (pin "2") (pinfunction "2_2") (pintype "passive"))
      (node (ref "SV1") (pin "VCC") (pinfunction "VCC_VCC") (pintype "power_in"))
      (node (ref "U1") (pin "8") (pinfunction "VCC_8") (pintype "bidirectional"))
    )
    (net (code "80") (name "unconnected-(IC2A-QH*-Pad9)") (class "Default")
      (node (ref "IC2") (pin "9") (pinfunction "QH*_9") (pintype "tri_state"))
    )
    (net (code "81") (name "unconnected-(IC4-OSCIN{slash}PA1-Pad5)") (class "Default")
      (node (ref "IC4") (pin "5") (pinfunction "OSCIN/PA1_5") (pintype "bidirectional"))
    )
    (net (code "82") (name "unconnected-(IC4-OSCOUT{slash}PA2-Pad6)") (class "Default")
      (node (ref "IC4") (pin "6") (pinfunction "OSCOUT/PA2_6") (pintype "bidirectional"))
    )
    (net (code "83") (name "unconnected-(J1-Pad2)") (class "Default")
      (node (ref "J1") (pin "2") (pinfunction "2_2") (pintype "passive"))
    )
    (net (code "84") (name "unconnected-(U1-SQW-Pad7)") (class "Default")
      (node (ref "U1") (pin "7") (pinfunction "SQW_7") (pintype "bidirectional"))
    )
  )
)
